# powerDistribution.net
KiCad netlist of a schematic drawn in EAGLE
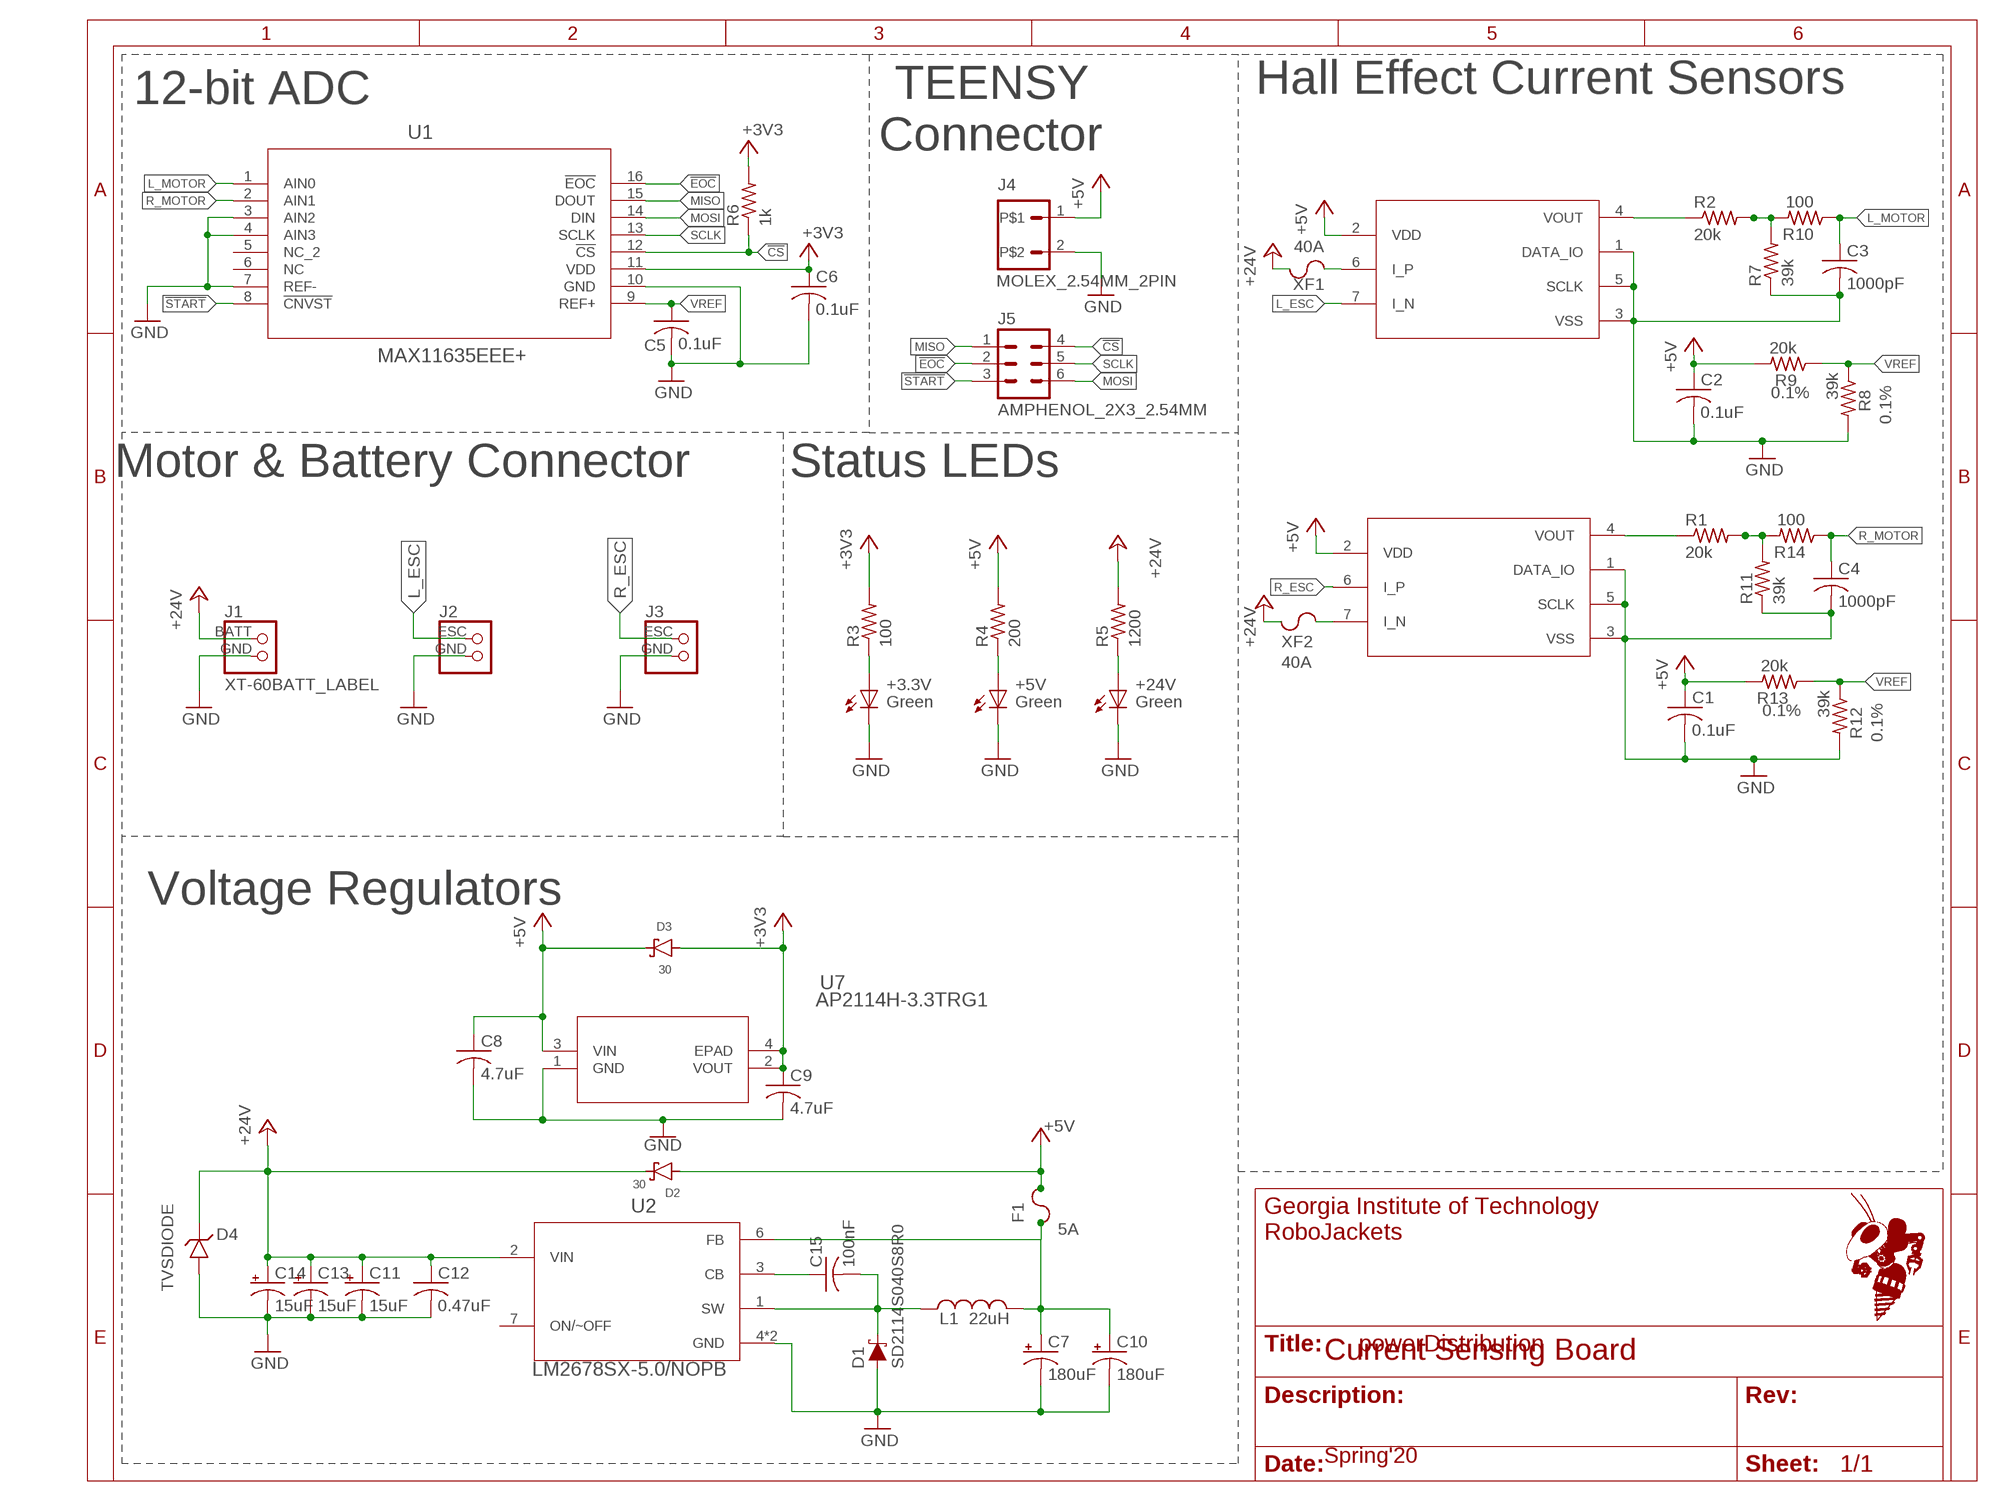
[diagram p0: schematic, sheet 1]

(export (version "E")
  (design (tool "Eeschema 10.0.6"))
  (components
    (comp (ref "+3.3V")
      (value "Green")
      (footprint "eagle-import:CHIP-LED0603")
      (libsource (lib "eagle-import") (part "LED-SMD"))
    )
    (comp (ref "+5V")
      (value "Green")
      (footprint "eagle-import:CHIP-LED0603")
      (libsource (lib "eagle-import") (part "LED-SMD"))
    )
    (comp (ref "+24V")
      (value "Green")
      (footprint "eagle-import:CHIP-LED0603")
      (libsource (lib "eagle-import") (part "LED-SMD"))
    )
    (comp (ref "C1")
      (value "0.1uF")
      (footprint "eagle-import:C0603")
      (libsource (lib "eagle-import") (part "C-USC0603"))
    )
    (comp (ref "C2")
      (value "0.1uF")
      (footprint "eagle-import:C0603")
      (libsource (lib "eagle-import") (part "C-USC0603"))
    )
    (comp (ref "C3")
      (value "1000pF")
      (footprint "eagle-import:C0603")
      (libsource (lib "eagle-import") (part "C-USC0603"))
    )
    (comp (ref "C4")
      (value "1000pF")
      (footprint "eagle-import:C0603")
      (libsource (lib "eagle-import") (part "C-USC0603"))
    )
    (comp (ref "C5")
      (value "0.1uF")
      (footprint "eagle-import:C0603")
      (libsource (lib "eagle-import") (part "C-USC0603"))
    )
    (comp (ref "C6")
      (value "0.1uF")
      (footprint "eagle-import:C0603")
      (libsource (lib "eagle-import") (part "C-USC0603"))
    )
    (comp (ref "C7")
      (value "180uF")
      (footprint "eagle-import:860010373009")
      (libsource (lib "eagle-import") (part "860010373009"))
    )
    (comp (ref "C8")
      (value "4.7uF")
      (footprint "eagle-import:C0603")
      (libsource (lib "eagle-import") (part "C-USC0603"))
    )
    (comp (ref "C9")
      (value "4.7uF")
      (footprint "eagle-import:C0603")
      (libsource (lib "eagle-import") (part "C-USC0603"))
    )
    (comp (ref "C10")
      (value "180uF")
      (footprint "eagle-import:860010373009")
      (libsource (lib "eagle-import") (part "860010373009"))
    )
    (comp (ref "C11")
      (value "15uF")
      (footprint "eagle-import:TR3E156M050C0300")
      (libsource (lib "eagle-import") (part "TR3E156M050C0300"))
    )
    (comp (ref "C12")
      (value "0.47uF")
      (footprint "eagle-import:C0603")
      (libsource (lib "eagle-import") (part "C-USC0603"))
    )
    (comp (ref "C13")
      (value "15uF")
      (footprint "eagle-import:TR3E156M050C0300")
      (libsource (lib "eagle-import") (part "TR3E156M050C0300"))
    )
    (comp (ref "C14")
      (value "15uF")
      (footprint "eagle-import:TR3E156M050C0300")
      (libsource (lib "eagle-import") (part "TR3E156M050C0300"))
    )
    (comp (ref "C15")
      (value "100nF")
      (footprint "eagle-import:C0603")
      (libsource (lib "eagle-import") (part "C-USC0603"))
    )
    (comp (ref "D1")
      (value "SD2114S040S8R0")
      (footprint "eagle-import:SD2114S040S8R0")
      (libsource (lib "eagle-import") (part "SD2114S040S8R0"))
    )
    (comp (ref "D2")
      (value "30")
      (footprint "eagle-import:DFLS130L-7")
      (libsource (lib "eagle-import") (part "DFLS130L-7"))
    )
    (comp (ref "D3")
      (value "30")
      (footprint "eagle-import:DFLS130L-7")
      (libsource (lib "eagle-import") (part "DFLS130L-7"))
    )
    (comp (ref "D4")
      (value "TVSDIODE")
      (footprint "eagle-import:TVSDIODE")
      (libsource (lib "eagle-import") (part "TVSDIODE"))
    )
    (comp (ref "F1")
      (value "5A")
      (footprint "eagle-import:ERB-RE5R00V")
      (libsource (lib "eagle-import") (part "ERB-RE5R00V"))
    )
    (comp (ref "J1")
      (value "XT-60BATT_LABEL")
      (footprint "eagle-import:XT-60")
      (libsource (lib "eagle-import") (part "XT-60BATT_LABEL"))
    )
    (comp (ref "J2")
      (value "CONNECTORESC_CONNECTOR")
      (footprint "eagle-import:ESC_CONNECT")
      (libsource (lib "eagle-import") (part "CONNECTORESC_CONNECTOR"))
    )
    (comp (ref "J3")
      (value "CONNECTORESC_CONNECTOR")
      (footprint "eagle-import:ESC_CONNECT")
      (libsource (lib "eagle-import") (part "CONNECTORESC_CONNECTOR"))
    )
    (comp (ref "J4")
      (value "MOLEX_2.54MM_2PIN")
      (footprint "eagle-import:MOLEX_2.54MM_2PIN")
      (libsource (lib "eagle-import") (part "MOLEX_2.54MM_2PIN"))
    )
    (comp (ref "J5")
      (value "AMPHENOL_2X3_2.54MM")
      (footprint "eagle-import:AMPHENOL_2X3_2.54MM")
      (libsource (lib "eagle-import") (part "AMPHENOL_2X3_2.54MM"))
    )
    (comp (ref "L1")
      (value "22uH")
      (footprint "eagle-import:INDUCTOR22")
      (libsource (lib "eagle-import") (part "7447709220"))
    )
    (comp (ref "R1")
      (value "20k")
      (footprint "eagle-import:R0603")
      (libsource (lib "eagle-import") (part "R-US_R0603"))
    )
    (comp (ref "R2")
      (value "20k")
      (footprint "eagle-import:R0603")
      (libsource (lib "eagle-import") (part "R-US_R0603"))
    )
    (comp (ref "R3")
      (value "100")
      (footprint "eagle-import:R0603")
      (libsource (lib "eagle-import") (part "R-US_R0603"))
    )
    (comp (ref "R4")
      (value "200")
      (footprint "eagle-import:R0603")
      (libsource (lib "eagle-import") (part "R-US_R0603"))
    )
    (comp (ref "R5")
      (value "1200")
      (footprint "eagle-import:R0603")
      (libsource (lib "eagle-import") (part "R-US_R0603"))
    )
    (comp (ref "R6")
      (value "1k")
      (footprint "eagle-import:R0603")
      (libsource (lib "eagle-import") (part "R-US_R0603"))
    )
    (comp (ref "R7")
      (value "39k")
      (footprint "eagle-import:R0603")
      (libsource (lib "eagle-import") (part "R-US_R0603"))
    )
    (comp (ref "R8")
      (value "39k")
      (footprint "eagle-import:R0603")
      (libsource (lib "eagle-import") (part "R-US_R0603"))
    )
    (comp (ref "R9")
      (value "20k")
      (footprint "eagle-import:R0603")
      (libsource (lib "eagle-import") (part "R-US_R0603"))
    )
    (comp (ref "R10")
      (value "100")
      (footprint "eagle-import:R0603")
      (libsource (lib "eagle-import") (part "R-US_R0603"))
    )
    (comp (ref "R11")
      (value "39k")
      (footprint "eagle-import:R0603")
      (libsource (lib "eagle-import") (part "R-US_R0603"))
    )
    (comp (ref "R12")
      (value "39k")
      (footprint "eagle-import:R0603")
      (libsource (lib "eagle-import") (part "R-US_R0603"))
    )
    (comp (ref "R13")
      (value "20k")
      (footprint "eagle-import:R0603")
      (libsource (lib "eagle-import") (part "R-US_R0603"))
    )
    (comp (ref "R14")
      (value "100")
      (footprint "eagle-import:R0603")
      (libsource (lib "eagle-import") (part "R-US_R0603"))
    )
    (comp (ref "U1")
      (value "MAX11635EEE+")
      (footprint "eagle-import:21-0055H_16_MXM")
      (libsource (lib "eagle-import") (part "MAX11635EEE+"))
    )
    (comp (ref "U2")
      (value "LM2678SX-5.0/NOPB")
      (footprint "eagle-import:TS7B")
      (libsource (lib "eagle-import") (part "LM2678SX-5.0/NOPB"))
    )
    (comp (ref "U3")
      (value "CQ2065")
      (footprint "eagle-import:974-1092-1")
      (libsource (lib "eagle-import") (part "CQ2065"))
    )
    (comp (ref "U4")
      (value "CQ2065")
      (footprint "eagle-import:974-1092-1")
      (libsource (lib "eagle-import") (part "CQ2065"))
    )
    (comp (ref "U7")
      (value "AP2114H-3.3TRG1")
      (footprint "eagle-import:SOT-223")
      (fields (field (name "MANUFACTURER_PART_NUMBER") "AP2114H3.3TRG1"))
      (libsource (lib "eagle-import") (part "AP2114H-3.3TRG1"))
    )
    (comp (ref "XF1")
      (value "40A")
      (footprint "eagle-import:3550")
      (libsource (lib "eagle-import") (part "3550(2)"))
    )
    (comp (ref "XF2")
      (value "40A")
      (footprint "eagle-import:3550")
      (libsource (lib "eagle-import") (part "3550(2)"))
    )
  )
  (nets
    (net (code "1") (name "+3V3") (class "Default")
      (node (ref "C6") (pin "1") (pinfunction "1_1") (pintype "passive"))
      (node (ref "C9") (pin "1") (pinfunction "1_1") (pintype "passive"))
      (node (ref "D3") (pin "1") (pinfunction "A_1") (pintype "passive"))
      (node (ref "R3") (pin "2") (pinfunction "2_2") (pintype "passive"))
      (node (ref "R6") (pin "2") (pinfunction "2_2") (pintype "passive"))
      (node (ref "U1") (pin "11") (pinfunction "VDD_11") (pintype "power_in"))
      (node (ref "U7") (pin "2") (pinfunction "VOUT_2") (pintype "output"))
      (node (ref "U7") (pin "4") (pinfunction "EPAD_4") (pintype "passive"))
    )
    (net (code "2") (name "+5V") (class "Default")
      (node (ref "C1") (pin "1") (pinfunction "1_1") (pintype "passive"))
      (node (ref "C2") (pin "1") (pinfunction "1_1") (pintype "passive"))
      (node (ref "C8") (pin "1") (pinfunction "1_1") (pintype "passive"))
      (node (ref "D2") (pin "1") (pinfunction "A_1") (pintype "passive"))
      (node (ref "D3") (pin "2") (pinfunction "C_2") (pintype "passive"))
      (node (ref "F1") (pin "2") (pinfunction "2_2") (pintype "bidirectional"))
      (node (ref "J4") (pin "1") (pinfunction "P$1_1") (pintype "bidirectional"))
      (node (ref "R13") (pin "2") (pinfunction "2_2") (pintype "passive"))
      (node (ref "R4") (pin "2") (pinfunction "2_2") (pintype "passive"))
      (node (ref "R9") (pin "2") (pinfunction "2_2") (pintype "passive"))
      (node (ref "U3") (pin "2") (pinfunction "VDD_2") (pintype "bidirectional"))
      (node (ref "U4") (pin "2") (pinfunction "VDD_2") (pintype "bidirectional"))
      (node (ref "U7") (pin "3") (pinfunction "VIN_3") (pintype "input"))
    )
    (net (code "3") (name "+24V") (class "Default")
      (node (ref "C11") (pin "1") (pinfunction "+_1") (pintype "passive"))
      (node (ref "C12") (pin "1") (pinfunction "1_1") (pintype "passive"))
      (node (ref "C13") (pin "1") (pinfunction "+_1") (pintype "passive"))
      (node (ref "C14") (pin "1") (pinfunction "+_1") (pintype "passive"))
      (node (ref "D2") (pin "2") (pinfunction "C_2") (pintype "passive"))
      (node (ref "D4") (pin "P$2") (pinfunction "C_P$2") (pintype "passive"))
      (node (ref "J1") (pin "BATT") (pinfunction "1_BATT") (pintype "passive"))
      (node (ref "R5") (pin "2") (pinfunction "2_2") (pintype "passive"))
      (node (ref "U2") (pin "2") (pinfunction "VIN_2") (pintype "input"))
      (node (ref "XF1") (pin "3") (pinfunction "2_3") (pintype "bidirectional"))
      (node (ref "XF1") (pin "4") (pinfunction "2_4") (pintype "bidirectional"))
      (node (ref "XF2") (pin "1") (pinfunction "1_1") (pintype "bidirectional"))
      (node (ref "XF2") (pin "2") (pinfunction "1_2") (pintype "bidirectional"))
    )
    (net (code "4") (name "/~{CS}") (class "Default")
      (node (ref "J5") (pin "4") (pinfunction "5_4") (pintype "passive"))
      (node (ref "R6") (pin "1") (pinfunction "1_1") (pintype "passive"))
      (node (ref "U1") (pin "12") (pinfunction "~{CS}_12") (pintype "passive"))
    )
    (net (code "5") (name "/~{EOC}") (class "Default")
      (node (ref "J5") (pin "2") (pinfunction "4_2") (pintype "passive"))
      (node (ref "U1") (pin "16") (pinfunction "~{EOC}_16") (pintype "passive"))
    )
    (net (code "6") (name "/~{START}") (class "Default")
      (node (ref "J5") (pin "3") (pinfunction "2_3") (pintype "passive"))
      (node (ref "U1") (pin "8") (pinfunction "~{CNVST}_8") (pintype "passive"))
    )
    (net (code "7") (name "GND") (class "Default")
      (node (ref "+24V") (pin "C") (pinfunction "K_C") (pintype "passive"))
      (node (ref "+3.3V") (pin "C") (pinfunction "K_C") (pintype "passive"))
      (node (ref "+5V") (pin "C") (pinfunction "K_C") (pintype "passive"))
      (node (ref "C1") (pin "2") (pinfunction "2_2") (pintype "passive"))
      (node (ref "C10") (pin "2") (pinfunction "-_2") (pintype "passive"))
      (node (ref "C11") (pin "2") (pinfunction "-_2") (pintype "passive"))
      (node (ref "C12") (pin "2") (pinfunction "2_2") (pintype "passive"))
      (node (ref "C13") (pin "2") (pinfunction "-_2") (pintype "passive"))
      (node (ref "C14") (pin "2") (pinfunction "-_2") (pintype "passive"))
      (node (ref "C2") (pin "2") (pinfunction "2_2") (pintype "passive"))
      (node (ref "C3") (pin "2") (pinfunction "2_2") (pintype "passive"))
      (node (ref "C4") (pin "2") (pinfunction "2_2") (pintype "passive"))
      (node (ref "C5") (pin "2") (pinfunction "2_2") (pintype "passive"))
      (node (ref "C6") (pin "2") (pinfunction "2_2") (pintype "passive"))
      (node (ref "C7") (pin "2") (pinfunction "-_2") (pintype "passive"))
      (node (ref "C8") (pin "2") (pinfunction "2_2") (pintype "passive"))
      (node (ref "C9") (pin "2") (pinfunction "2_2") (pintype "passive"))
      (node (ref "D1") (pin "1") (pinfunction "A_1") (pintype "passive"))
      (node (ref "D4") (pin "P$1") (pinfunction "A_P$1") (pintype "passive"))
      (node (ref "J1") (pin "GND") (pinfunction "2_GND") (pintype "passive"))
      (node (ref "J2") (pin "GND") (pinfunction "2_GND") (pintype "passive"))
      (node (ref "J3") (pin "GND") (pinfunction "2_GND") (pintype "passive"))
      (node (ref "J4") (pin "2") (pinfunction "P$2_2") (pintype "bidirectional"))
      (node (ref "R11") (pin "1") (pinfunction "1_1") (pintype "passive"))
      (node (ref "R12") (pin "2") (pinfunction "2_2") (pintype "passive"))
      (node (ref "R7") (pin "1") (pinfunction "1_1") (pintype "passive"))
      (node (ref "R8") (pin "2") (pinfunction "2_2") (pintype "passive"))
      (node (ref "U1") (pin "10") (pinfunction "GND_10") (pintype "power_in"))
      (node (ref "U1") (pin "3") (pinfunction "AIN2_3") (pintype "input"))
      (node (ref "U1") (pin "4") (pinfunction "AIN3_4") (pintype "input"))
      (node (ref "U1") (pin "7") (pinfunction "REF-_7") (pintype "passive"))
      (node (ref "U2") (pin "4") (pinfunction "GND_4") (pintype "passive"))
      (node (ref "U2") (pin "8") (pinfunction "GND_8") (pintype "passive"))
      (node (ref "U3") (pin "1") (pinfunction "DATA_IO_1") (pintype "bidirectional"))
      (node (ref "U3") (pin "3") (pinfunction "VSS_3") (pintype "bidirectional"))
      (node (ref "U3") (pin "5") (pinfunction "SCLK_5") (pintype "bidirectional"))
      (node (ref "U4") (pin "1") (pinfunction "DATA_IO_1") (pintype "bidirectional"))
      (node (ref "U4") (pin "3") (pinfunction "VSS_3") (pintype "bidirectional"))
      (node (ref "U4") (pin "5") (pinfunction "SCLK_5") (pintype "bidirectional"))
      (node (ref "U7") (pin "1") (pinfunction "GND_1") (pintype "power_in"))
    )
    (net (code "8") (name "L_ESC") (class "Default")
      (node (ref "J2") (pin "ESC") (pinfunction "1_ESC") (pintype "passive"))
      (node (ref "U3") (pin "7") (pinfunction "I_N_7") (pintype "bidirectional"))
    )
    (net (code "9") (name "L_MOTOR") (class "Default")
      (node (ref "C3") (pin "1") (pinfunction "1_1") (pintype "passive"))
      (node (ref "R10") (pin "1") (pinfunction "1_1") (pintype "passive"))
      (node (ref "U1") (pin "1") (pinfunction "AIN0_1") (pintype "input"))
    )
    (net (code "10") (name "MISO") (class "Default")
      (node (ref "J5") (pin "1") (pinfunction "6_1") (pintype "passive"))
      (node (ref "U1") (pin "15") (pinfunction "DOUT_15") (pintype "output"))
    )
    (net (code "11") (name "MOSI") (class "Default")
      (node (ref "J5") (pin "6") (pinfunction "1_6") (pintype "passive"))
      (node (ref "U1") (pin "14") (pinfunction "DIN_14") (pintype "input"))
    )
    (net (code "12") (name "Net-(+3.3V-PadA)") (class "Default")
      (node (ref "+3.3V") (pin "A") (pinfunction "A_A") (pintype "passive"))
      (node (ref "R3") (pin "1") (pinfunction "1_1") (pintype "passive"))
    )
    (net (code "13") (name "Net-(+5V-PadA)") (class "Default")
      (node (ref "+5V") (pin "A") (pinfunction "A_A") (pintype "passive"))
      (node (ref "R4") (pin "1") (pinfunction "1_1") (pintype "passive"))
    )
    (net (code "14") (name "Net-(+24V-PadA)") (class "Default")
      (node (ref "+24V") (pin "A") (pinfunction "A_A") (pintype "passive"))
      (node (ref "R5") (pin "1") (pinfunction "1_1") (pintype "passive"))
    )
    (net (code "15") (name "Net-(C10-+)") (class "Default")
      (node (ref "C10") (pin "1") (pinfunction "+_1") (pintype "passive"))
      (node (ref "C7") (pin "1") (pinfunction "+_1") (pintype "passive"))
      (node (ref "F1") (pin "1") (pinfunction "1_1") (pintype "bidirectional"))
      (node (ref "L1") (pin "2") (pinfunction "2_2") (pintype "passive"))
      (node (ref "U2") (pin "6") (pinfunction "FB_6") (pintype "passive"))
    )
    (net (code "16") (name "Net-(D1-C)") (class "Default")
      (node (ref "C15") (pin "2") (pinfunction "2_2") (pintype "passive"))
      (node (ref "D1") (pin "2") (pinfunction "C_2") (pintype "passive"))
      (node (ref "L1") (pin "1") (pinfunction "1_1") (pintype "passive"))
      (node (ref "U2") (pin "1") (pinfunction "SW_1") (pintype "output"))
    )
    (net (code "17") (name "Net-(R1-Pad2)") (class "Default")
      (node (ref "R1") (pin "2") (pinfunction "2_2") (pintype "passive"))
      (node (ref "R11") (pin "2") (pinfunction "2_2") (pintype "passive"))
      (node (ref "R14") (pin "2") (pinfunction "2_2") (pintype "passive"))
    )
    (net (code "18") (name "Net-(R10-Pad2)") (class "Default")
      (node (ref "R10") (pin "2") (pinfunction "2_2") (pintype "passive"))
      (node (ref "R2") (pin "2") (pinfunction "2_2") (pintype "passive"))
      (node (ref "R7") (pin "2") (pinfunction "2_2") (pintype "passive"))
    )
    (net (code "19") (name "Net-(U2-CB)") (class "Default")
      (node (ref "C15") (pin "1") (pinfunction "1_1") (pintype "passive"))
      (node (ref "U2") (pin "3") (pinfunction "CB_3") (pintype "passive"))
    )
    (net (code "20") (name "Net-(U3-I_P)") (class "Default")
      (node (ref "U3") (pin "6") (pinfunction "I_P_6") (pintype "bidirectional"))
      (node (ref "XF1") (pin "1") (pinfunction "1_1") (pintype "bidirectional"))
      (node (ref "XF1") (pin "2") (pinfunction "1_2") (pintype "bidirectional"))
    )
    (net (code "21") (name "Net-(U3-VOUT)") (class "Default")
      (node (ref "R2") (pin "1") (pinfunction "1_1") (pintype "passive"))
      (node (ref "U3") (pin "4") (pinfunction "VOUT_4") (pintype "bidirectional"))
    )
    (net (code "22") (name "Net-(U4-I_N)") (class "Default")
      (node (ref "U4") (pin "7") (pinfunction "I_N_7") (pintype "bidirectional"))
      (node (ref "XF2") (pin "3") (pinfunction "2_3") (pintype "bidirectional"))
      (node (ref "XF2") (pin "4") (pinfunction "2_4") (pintype "bidirectional"))
    )
    (net (code "23") (name "Net-(U4-VOUT)") (class "Default")
      (node (ref "R1") (pin "1") (pinfunction "1_1") (pintype "passive"))
      (node (ref "U4") (pin "4") (pinfunction "VOUT_4") (pintype "bidirectional"))
    )
    (net (code "24") (name "R_ESC") (class "Default")
      (node (ref "J3") (pin "ESC") (pinfunction "1_ESC") (pintype "passive"))
      (node (ref "U4") (pin "6") (pinfunction "I_P_6") (pintype "bidirectional"))
    )
    (net (code "25") (name "R_MOTOR") (class "Default")
      (node (ref "C4") (pin "1") (pinfunction "1_1") (pintype "passive"))
      (node (ref "R14") (pin "1") (pinfunction "1_1") (pintype "passive"))
      (node (ref "U1") (pin "2") (pinfunction "AIN1_2") (pintype "input"))
    )
    (net (code "26") (name "SCLK") (class "Default")
      (node (ref "J5") (pin "5") (pinfunction "3_5") (pintype "passive"))
      (node (ref "U1") (pin "13") (pinfunction "SCLK_13") (pintype "passive"))
    )
    (net (code "27") (name "VREF") (class "Default")
      (node (ref "C5") (pin "1") (pinfunction "1_1") (pintype "passive"))
      (node (ref "R12") (pin "1") (pinfunction "1_1") (pintype "passive"))
      (node (ref "R13") (pin "1") (pinfunction "1_1") (pintype "passive"))
      (node (ref "R8") (pin "1") (pinfunction "1_1") (pintype "passive"))
      (node (ref "R9") (pin "1") (pinfunction "1_1") (pintype "passive"))
      (node (ref "U1") (pin "9") (pinfunction "REF+_9") (pintype "passive"))
    )
    (net (code "28") (name "unconnected-(U1-NC-Pad6)") (class "Default")
      (node (ref "U1") (pin "6") (pinfunction "NC_6") (pintype "no_connect"))
    )
    (net (code "29") (name "unconnected-(U1-NC_2-Pad5)") (class "Default")
      (node (ref "U1") (pin "5") (pinfunction "NC_2_5") (pintype "no_connect"))
    )
    (net (code "30") (name "unconnected-(U2-ON{slash}~{OFF}-Pad7)") (class "Default")
      (node (ref "U2") (pin "7") (pinfunction "ON/~{OFF}_7") (pintype "passive"))
    )
  )
)
